# FX-Flash_DIP_rev_B.net
KiCad netlist of a schematic drawn in EAGLE
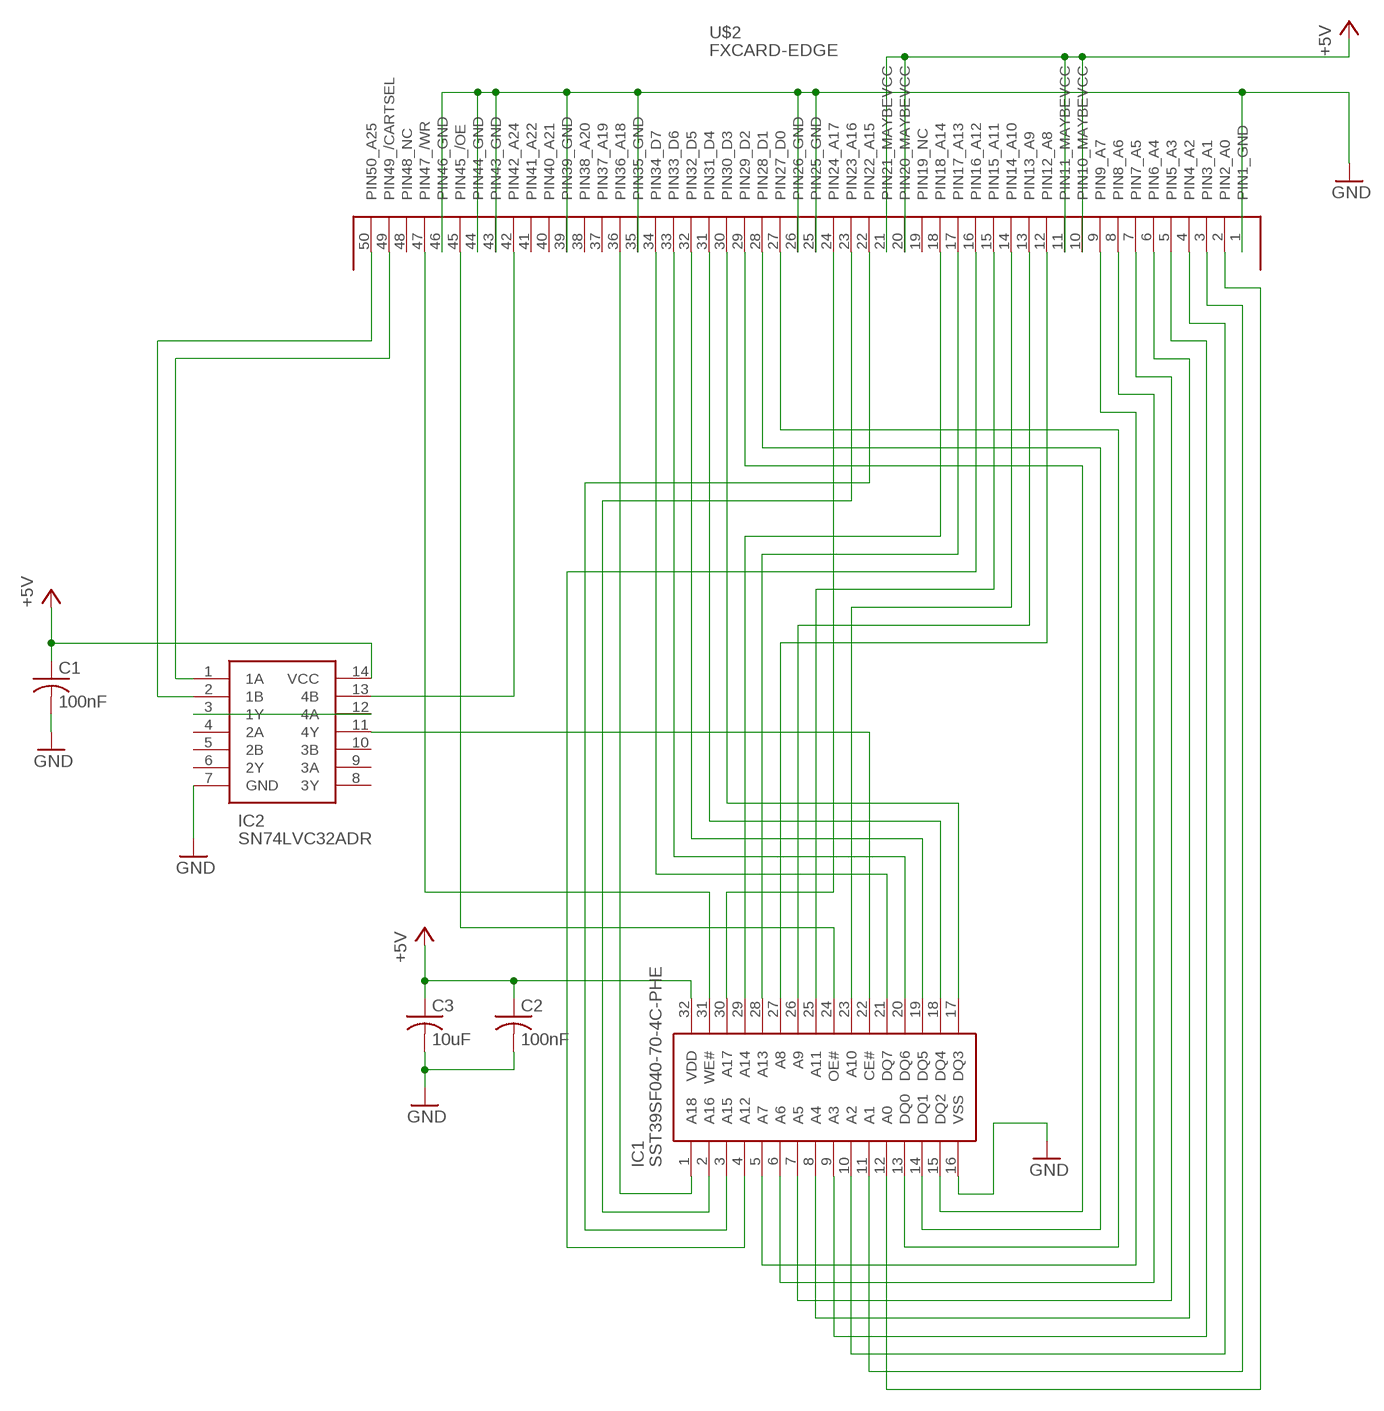
[diagram p0: schematic, sheet 1]

(export (version "E")
  (design (tool "Eeschema 10.0.6"))
  (components
    (comp (ref "C1")
      (value "100nF")
      (footprint "eagle-import:C0402")
      (libsource (lib "eagle-import") (part "C-USC0402"))
    )
    (comp (ref "C2")
      (value "100nF")
      (footprint "eagle-import:C0402")
      (libsource (lib "eagle-import") (part "C-USC0402"))
    )
    (comp (ref "C3")
      (value "10uF")
      (footprint "eagle-import:C0805")
      (libsource (lib "eagle-import") (part "resistor_348_C-USC0805"))
    )
    (comp (ref "IC1")
      (value "SST39SF040-70-4C-PHE")
      (footprint "eagle-import:DIP1556W56P254L4191H508Q32N")
      (fields
        (field (name "MOUSER_PART_NUMBER") "804-39SF0407CPHE")
        (field (name "RS_PART_NUMBER") "8104037P")
      )
      (libsource (lib "eagle-import") (part "SST39SF040-70-4C-PHE"))
    )
    (comp (ref "IC2")
      (value "SN74LVC32ADR")
      (footprint "eagle-import:SOIC127P600X175-14N")
      (fields (field (name "MOUSER_PART_NUMBER") "595-SN74LVC32ADR"))
      (libsource (lib "eagle-import") (part "SN74LVC32ADR"))
    )
    (comp (ref "U$2")
      (value "FXCARD-EDGE")
      (footprint "eagle-import:FXCARD-EDGE")
      (libsource (lib "eagle-import") (part "FXCARD-EDGE"))
    )
  )
  (nets
    (net (code "1") (name "+5V") (class "Default")
      (node (ref "C1") (pin "1") (pinfunction "1_1") (pintype "passive"))
      (node (ref "C2") (pin "1") (pinfunction "1_1") (pintype "passive"))
      (node (ref "C3") (pin "1") (pinfunction "1_1") (pintype "passive"))
      (node (ref "IC1") (pin "32") (pinfunction "VDD_32") (pintype "bidirectional"))
      (node (ref "IC2") (pin "14") (pinfunction "VCC_14") (pintype "bidirectional"))
      (node (ref "U$2") (pin "10") (pinfunction "PIN10_MAYBEVCC_10") (pintype "bidirectional"))
      (node (ref "U$2") (pin "11") (pinfunction "PIN11_MAYBEVCC_11") (pintype "bidirectional"))
      (node (ref "U$2") (pin "20") (pinfunction "PIN20_MAYBEVCC_20") (pintype "bidirectional"))
      (node (ref "U$2") (pin "21") (pinfunction "PIN21_MAYBEVCC_21") (pintype "bidirectional"))
    )
    (net (code "2") (name "GND") (class "Default")
      (node (ref "C1") (pin "2") (pinfunction "2_2") (pintype "passive"))
      (node (ref "C2") (pin "2") (pinfunction "2_2") (pintype "passive"))
      (node (ref "C3") (pin "2") (pinfunction "2_2") (pintype "passive"))
      (node (ref "IC1") (pin "16") (pinfunction "VSS_16") (pintype "bidirectional"))
      (node (ref "IC2") (pin "7") (pinfunction "GND_7") (pintype "bidirectional"))
      (node (ref "U$2") (pin "1") (pinfunction "PIN1_GND_1") (pintype "power_in"))
      (node (ref "U$2") (pin "25") (pinfunction "PIN25_GND_25") (pintype "power_in"))
      (node (ref "U$2") (pin "26") (pinfunction "PIN26_GND_26") (pintype "power_in"))
      (node (ref "U$2") (pin "35") (pinfunction "PIN35_GND_35") (pintype "power_in"))
      (node (ref "U$2") (pin "39") (pinfunction "PIN39_GND_39") (pintype "power_in"))
      (node (ref "U$2") (pin "43") (pinfunction "PIN43_GND_43") (pintype "power_in"))
      (node (ref "U$2") (pin "44") (pinfunction "PIN44_GND_44") (pintype "power_in"))
      (node (ref "U$2") (pin "46") (pinfunction "PIN46_GND_46") (pintype "power_in"))
    )
    (net (code "3") (name "Net-(IC1-A0)") (class "Default")
      (node (ref "IC1") (pin "12") (pinfunction "A0_12") (pintype "bidirectional"))
      (node (ref "U$2") (pin "2") (pinfunction "PIN2_A0_2") (pintype "bidirectional"))
    )
    (net (code "4") (name "Net-(IC1-A1)") (class "Default")
      (node (ref "IC1") (pin "11") (pinfunction "A1_11") (pintype "bidirectional"))
      (node (ref "U$2") (pin "3") (pinfunction "PIN3_A1_3") (pintype "bidirectional"))
    )
    (net (code "5") (name "Net-(IC1-A2)") (class "Default")
      (node (ref "IC1") (pin "10") (pinfunction "A2_10") (pintype "bidirectional"))
      (node (ref "U$2") (pin "4") (pinfunction "PIN4_A2_4") (pintype "bidirectional"))
    )
    (net (code "6") (name "Net-(IC1-A3)") (class "Default")
      (node (ref "IC1") (pin "9") (pinfunction "A3_9") (pintype "bidirectional"))
      (node (ref "U$2") (pin "5") (pinfunction "PIN5_A3_5") (pintype "bidirectional"))
    )
    (net (code "7") (name "Net-(IC1-A4)") (class "Default")
      (node (ref "IC1") (pin "8") (pinfunction "A4_8") (pintype "bidirectional"))
      (node (ref "U$2") (pin "6") (pinfunction "PIN6_A4_6") (pintype "bidirectional"))
    )
    (net (code "8") (name "Net-(IC1-A5)") (class "Default")
      (node (ref "IC1") (pin "7") (pinfunction "A5_7") (pintype "bidirectional"))
      (node (ref "U$2") (pin "7") (pinfunction "PIN7_A5_7") (pintype "bidirectional"))
    )
    (net (code "9") (name "Net-(IC1-A6)") (class "Default")
      (node (ref "IC1") (pin "6") (pinfunction "A6_6") (pintype "bidirectional"))
      (node (ref "U$2") (pin "8") (pinfunction "PIN8_A6_8") (pintype "bidirectional"))
    )
    (net (code "10") (name "Net-(IC1-A7)") (class "Default")
      (node (ref "IC1") (pin "5") (pinfunction "A7_5") (pintype "bidirectional"))
      (node (ref "U$2") (pin "9") (pinfunction "PIN9_A7_9") (pintype "bidirectional"))
    )
    (net (code "11") (name "Net-(IC1-A8)") (class "Default")
      (node (ref "IC1") (pin "27") (pinfunction "A8_27") (pintype "bidirectional"))
      (node (ref "U$2") (pin "12") (pinfunction "PIN12_A8_12") (pintype "bidirectional"))
    )
    (net (code "12") (name "Net-(IC1-A9)") (class "Default")
      (node (ref "IC1") (pin "26") (pinfunction "A9_26") (pintype "bidirectional"))
      (node (ref "U$2") (pin "13") (pinfunction "PIN13_A9_13") (pintype "bidirectional"))
    )
    (net (code "13") (name "Net-(IC1-A10)") (class "Default")
      (node (ref "IC1") (pin "23") (pinfunction "A10_23") (pintype "bidirectional"))
      (node (ref "U$2") (pin "14") (pinfunction "PIN14_A10_14") (pintype "bidirectional"))
    )
    (net (code "14") (name "Net-(IC1-A11)") (class "Default")
      (node (ref "IC1") (pin "25") (pinfunction "A11_25") (pintype "bidirectional"))
      (node (ref "U$2") (pin "15") (pinfunction "PIN15_A11_15") (pintype "bidirectional"))
    )
    (net (code "15") (name "Net-(IC1-A12)") (class "Default")
      (node (ref "IC1") (pin "4") (pinfunction "A12_4") (pintype "bidirectional"))
      (node (ref "U$2") (pin "16") (pinfunction "PIN16_A12_16") (pintype "bidirectional"))
    )
    (net (code "16") (name "Net-(IC1-A13)") (class "Default")
      (node (ref "IC1") (pin "28") (pinfunction "A13_28") (pintype "bidirectional"))
      (node (ref "U$2") (pin "17") (pinfunction "PIN17_A13_17") (pintype "bidirectional"))
    )
    (net (code "17") (name "Net-(IC1-A14)") (class "Default")
      (node (ref "IC1") (pin "29") (pinfunction "A14_29") (pintype "bidirectional"))
      (node (ref "U$2") (pin "18") (pinfunction "PIN18_A14_18") (pintype "bidirectional"))
    )
    (net (code "18") (name "Net-(IC1-A15)") (class "Default")
      (node (ref "IC1") (pin "3") (pinfunction "A15_3") (pintype "bidirectional"))
      (node (ref "U$2") (pin "22") (pinfunction "PIN22_A15_22") (pintype "bidirectional"))
    )
    (net (code "19") (name "Net-(IC1-A16)") (class "Default")
      (node (ref "IC1") (pin "2") (pinfunction "A16_2") (pintype "bidirectional"))
      (node (ref "U$2") (pin "23") (pinfunction "PIN23_A16_23") (pintype "bidirectional"))
    )
    (net (code "20") (name "Net-(IC1-A17)") (class "Default")
      (node (ref "IC1") (pin "30") (pinfunction "A17_30") (pintype "bidirectional"))
      (node (ref "U$2") (pin "24") (pinfunction "PIN24_A17_24") (pintype "bidirectional"))
    )
    (net (code "21") (name "Net-(IC1-A18)") (class "Default")
      (node (ref "IC1") (pin "1") (pinfunction "A18_1") (pintype "bidirectional"))
      (node (ref "U$2") (pin "36") (pinfunction "PIN36_A18_36") (pintype "bidirectional"))
    )
    (net (code "22") (name "Net-(IC1-CE#)") (class "Default")
      (node (ref "IC1") (pin "22") (pinfunction "CE#_22") (pintype "bidirectional"))
      (node (ref "IC2") (pin "11") (pinfunction "4Y_11") (pintype "bidirectional"))
    )
    (net (code "23") (name "Net-(IC1-DQ0)") (class "Default")
      (node (ref "IC1") (pin "13") (pinfunction "DQ0_13") (pintype "bidirectional"))
      (node (ref "U$2") (pin "27") (pinfunction "PIN27_D0_27") (pintype "bidirectional"))
    )
    (net (code "24") (name "Net-(IC1-DQ1)") (class "Default")
      (node (ref "IC1") (pin "14") (pinfunction "DQ1_14") (pintype "bidirectional"))
      (node (ref "U$2") (pin "28") (pinfunction "PIN28_D1_28") (pintype "bidirectional"))
    )
    (net (code "25") (name "Net-(IC1-DQ2)") (class "Default")
      (node (ref "IC1") (pin "15") (pinfunction "DQ2_15") (pintype "bidirectional"))
      (node (ref "U$2") (pin "29") (pinfunction "PIN29_D2_29") (pintype "bidirectional"))
    )
    (net (code "26") (name "Net-(IC1-DQ3)") (class "Default")
      (node (ref "IC1") (pin "17") (pinfunction "DQ3_17") (pintype "bidirectional"))
      (node (ref "U$2") (pin "30") (pinfunction "PIN30_D3_30") (pintype "bidirectional"))
    )
    (net (code "27") (name "Net-(IC1-DQ4)") (class "Default")
      (node (ref "IC1") (pin "18") (pinfunction "DQ4_18") (pintype "bidirectional"))
      (node (ref "U$2") (pin "31") (pinfunction "PIN31_D4_31") (pintype "bidirectional"))
    )
    (net (code "28") (name "Net-(IC1-DQ5)") (class "Default")
      (node (ref "IC1") (pin "19") (pinfunction "DQ5_19") (pintype "bidirectional"))
      (node (ref "U$2") (pin "32") (pinfunction "PIN32_D5_32") (pintype "bidirectional"))
    )
    (net (code "29") (name "Net-(IC1-DQ6)") (class "Default")
      (node (ref "IC1") (pin "20") (pinfunction "DQ6_20") (pintype "bidirectional"))
      (node (ref "U$2") (pin "33") (pinfunction "PIN33_D6_33") (pintype "bidirectional"))
    )
    (net (code "30") (name "Net-(IC1-DQ7)") (class "Default")
      (node (ref "IC1") (pin "21") (pinfunction "DQ7_21") (pintype "bidirectional"))
      (node (ref "U$2") (pin "34") (pinfunction "PIN34_D7_34") (pintype "bidirectional"))
    )
    (net (code "31") (name "Net-(IC1-OE#)") (class "Default")
      (node (ref "IC1") (pin "24") (pinfunction "OE#_24") (pintype "bidirectional"))
      (node (ref "U$2") (pin "45") (pinfunction "PIN45_/OE_45") (pintype "bidirectional"))
    )
    (net (code "32") (name "Net-(IC1-WE#)") (class "Default")
      (node (ref "IC1") (pin "31") (pinfunction "WE#_31") (pintype "bidirectional"))
      (node (ref "U$2") (pin "47") (pinfunction "PIN47_/WR_47") (pintype "bidirectional"))
    )
    (net (code "33") (name "Net-(IC2-1A)") (class "Default")
      (node (ref "IC2") (pin "1") (pinfunction "1A_1") (pintype "bidirectional"))
      (node (ref "U$2") (pin "49") (pinfunction "PIN49_/CARTSEL_49") (pintype "bidirectional"))
    )
    (net (code "34") (name "Net-(IC2-1B)") (class "Default")
      (node (ref "IC2") (pin "2") (pinfunction "1B_2") (pintype "bidirectional"))
      (node (ref "U$2") (pin "50") (pinfunction "PIN50_A25_50") (pintype "bidirectional"))
    )
    (net (code "35") (name "Net-(IC2-1Y)") (class "Default")
      (node (ref "IC2") (pin "12") (pinfunction "4A_12") (pintype "bidirectional"))
      (node (ref "IC2") (pin "3") (pinfunction "1Y_3") (pintype "bidirectional"))
    )
    (net (code "36") (name "Net-(IC2-4B)") (class "Default")
      (node (ref "IC2") (pin "13") (pinfunction "4B_13") (pintype "bidirectional"))
      (node (ref "U$2") (pin "42") (pinfunction "PIN42_A24_42") (pintype "bidirectional"))
    )
    (net (code "37") (name "unconnected-(IC2-2A-Pad4)") (class "Default")
      (node (ref "IC2") (pin "4") (pinfunction "2A_4") (pintype "bidirectional"))
    )
    (net (code "38") (name "unconnected-(IC2-2B-Pad5)") (class "Default")
      (node (ref "IC2") (pin "5") (pinfunction "2B_5") (pintype "bidirectional"))
    )
    (net (code "39") (name "unconnected-(IC2-2Y-Pad6)") (class "Default")
      (node (ref "IC2") (pin "6") (pinfunction "2Y_6") (pintype "bidirectional"))
    )
    (net (code "40") (name "unconnected-(IC2-3A-Pad9)") (class "Default")
      (node (ref "IC2") (pin "9") (pinfunction "3A_9") (pintype "bidirectional"))
    )
    (net (code "41") (name "unconnected-(IC2-3B-Pad10)") (class "Default")
      (node (ref "IC2") (pin "10") (pinfunction "3B_10") (pintype "bidirectional"))
    )
    (net (code "42") (name "unconnected-(IC2-3Y-Pad8)") (class "Default")
      (node (ref "IC2") (pin "8") (pinfunction "3Y_8") (pintype "bidirectional"))
    )
    (net (code "43") (name "unconnected-(U$2-PIN19_NC-Pad19)") (class "Default")
      (node (ref "U$2") (pin "19") (pinfunction "PIN19_NC_19") (pintype "bidirectional"))
    )
    (net (code "44") (name "unconnected-(U$2-PIN37_A19-Pad37)") (class "Default")
      (node (ref "U$2") (pin "37") (pinfunction "PIN37_A19_37") (pintype "bidirectional"))
    )
    (net (code "45") (name "unconnected-(U$2-PIN38_A20-Pad38)") (class "Default")
      (node (ref "U$2") (pin "38") (pinfunction "PIN38_A20_38") (pintype "bidirectional"))
    )
    (net (code "46") (name "unconnected-(U$2-PIN40_A21-Pad40)") (class "Default")
      (node (ref "U$2") (pin "40") (pinfunction "PIN40_A21_40") (pintype "bidirectional"))
    )
    (net (code "47") (name "unconnected-(U$2-PIN41_A22-Pad41)") (class "Default")
      (node (ref "U$2") (pin "41") (pinfunction "PIN41_A22_41") (pintype "bidirectional"))
    )
    (net (code "48") (name "unconnected-(U$2-PIN48_NC-Pad48)") (class "Default")
      (node (ref "U$2") (pin "48") (pinfunction "PIN48_NC_48") (pintype "bidirectional"))
    )
  )
)
